# S10_Reset_Logic.net
KiCad netlist of a schematic drawn in Altium Designer
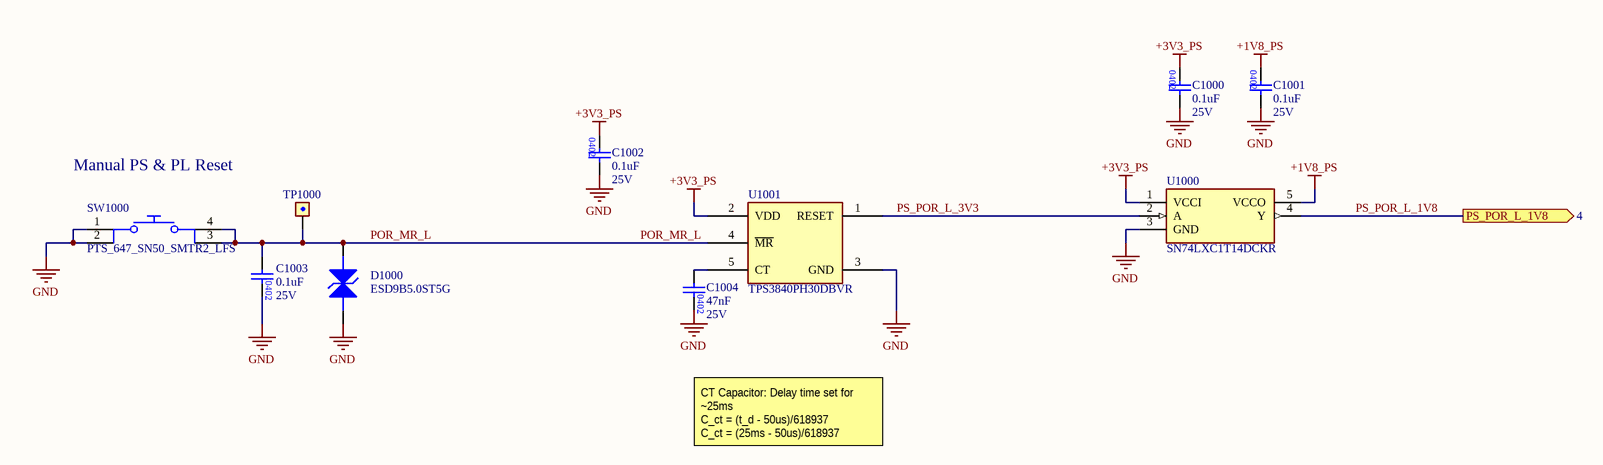
[diagram p0: S10_Reset_Logic.SchDoc]

(export (version "E")
  (design (tool "Eeschema 10.0.6"))
  (components
    (comp (ref "C1000")
      (value "0.1uF")
      (footprint "CAP0402")
      (description "CAP CER 0.1UF 25V X5R 0402")
      (fields
        (field (name "MANUFACTURER") "Samsung Electro-Mechanics")
        (field (name "TOLERANCE") "10%")
        (field (name "VOLTAGE RATING") "25V")
      )
      (libsource (lib "OpenCore_Sch_Lib") (part "CAP_CL05A104KA5NNNC"))
    )
    (comp (ref "C1001")
      (value "0.1uF")
      (footprint "CAP0402")
      (description "CAP CER 0.1UF 25V X5R 0402")
      (fields
        (field (name "MANUFACTURER") "Samsung Electro-Mechanics")
        (field (name "TOLERANCE") "10%")
        (field (name "VOLTAGE RATING") "25V")
      )
      (libsource (lib "OpenCore_Sch_Lib") (part "CAP_CL05A104KA5NNNC"))
    )
    (comp (ref "C1002")
      (value "0.1uF")
      (footprint "CAP0402")
      (description "CAP CER 0.1UF 25V X5R 0402")
      (fields
        (field (name "MANUFACTURER") "Samsung Electro-Mechanics")
        (field (name "TOLERANCE") "10%")
        (field (name "VOLTAGE RATING") "25V")
      )
      (libsource (lib "OpenCore_Sch_Lib") (part "CAP_CL05A104KA5NNNC"))
    )
    (comp (ref "C1003")
      (value "0.1uF")
      (footprint "CAP0402")
      (description "CAP CER 0.1UF 25V X5R 0402")
      (fields
        (field (name "MANUFACTURER") "Samsung Electro-Mechanics")
        (field (name "TOLERANCE") "10%")
        (field (name "VOLTAGE RATING") "25V")
      )
      (libsource (lib "OpenCore_Sch_Lib") (part "CAP_CL05A104KA5NNNC"))
    )
    (comp (ref "C1004")
      (value "47nF")
      (footprint "CAP0402")
      (description "CAP CER 0.047UF 25V X7R 0402")
      (fields
        (field (name "MANUFACTURER") "Murata Electronics")
        (field (name "TOLERANCE") "10%")
        (field (name "VOLTAGE RATING") "25V")
      )
      (libsource (lib "OpenCore_Sch_Lib") (part "CAP_GRM155R71E473KA88D"))
    )
    (comp (ref "D1000")
      (value "ESD9B5.0ST5G")
      (footprint "ONSEMI_SOD-923")
      (description "TVS DIODE 5VWM SOD923")
      (fields (field (name "MANUFACTURER PART NUMBER") "ESD9B5.0ST5G"))
      (libsource (lib "OpenCore_Sch_Lib") (part "ESD9B5.0ST5G"))
    )
    (comp (ref "SW1000")
      (value "PTS_647_SN50_SMTR2_LFS")
      (footprint "TACTILE_SW_4.5MM")
      (description "SWITCH TACTILE SPST-NO 0.05A 12V")
      (libsource (lib "OpenCore_Sch_Lib") (part "PTS_647_SN50_SMTR2_LFS"))
    )
    (comp (ref "TP1000")
      (value "1mm Round Pad Testpoint")
      (footprint "TP_1MM")
      (libsource (lib "OpenCore_Sch_Lib") (part "TP_1MM"))
    )
    (comp (ref "U1000")
      (value "SN74LXC1T14DCKR")
      (footprint "TI_SC70_DCK0005A")
      (description "IC TRANSLATOR UNIDIR SC70-5")
      (libsource (lib "OpenCore_Sch_Lib") (part "SN74LXC1T14DCKR"))
    )
    (comp (ref "U1001")
      (value "TPS3840PH30DBVR")
      (footprint "TI_SOT23_DBV0005A")
      (description "IC SUPERVISOR 1 CHANNEL SOT23-5")
      (libsource (lib "OpenCore_Sch_Lib") (part "TPS3840PH30DBVR"))
    )
  )
  (nets
    (net (code "1") (name "+1V8_PS") (class "Default")
      (node (ref "C1001") (pin "1") (pinfunction "1_1") (pintype "passive"))
      (node (ref "U1000") (pin "5") (pinfunction "VCCO_5") (pintype "power_in"))
    )
    (net (code "2") (name "+3V3_PS") (class "Default")
      (node (ref "C1000") (pin "1") (pinfunction "1_1") (pintype "passive"))
      (node (ref "C1002") (pin "1") (pinfunction "1_1") (pintype "passive"))
      (node (ref "U1000") (pin "1") (pinfunction "VCCI_1") (pintype "power_in"))
      (node (ref "U1001") (pin "2") (pinfunction "VDD_2") (pintype "passive"))
    )
    (net (code "3") (name "/POR_MR_L") (class "Default")
      (node (ref "C1003") (pin "1") (pinfunction "1_1") (pintype "passive"))
      (node (ref "D1000") (pin "A") (pinfunction "Anode_A") (pintype "passive"))
      (node (ref "SW1000") (pin "3") (pinfunction "3_3") (pintype "passive"))
      (node (ref "SW1000") (pin "4") (pinfunction "4_4") (pintype "passive"))
      (node (ref "TP1000") (pin "1") (pinfunction "1_1") (pintype "passive"))
      (node (ref "U1001") (pin "4") (pinfunction "~{MR}_4") (pintype "passive"))
    )
    (net (code "4") (name "/PS_POR_L_1V8") (class "Default")
      (node (ref "U1000") (pin "4") (pinfunction "Y_4") (pintype "output"))
    )
    (net (code "5") (name "/PS_POR_L_3V3") (class "Default")
      (node (ref "U1000") (pin "2") (pinfunction "A_2") (pintype "input"))
      (node (ref "U1001") (pin "1") (pinfunction "RESET_1") (pintype "passive"))
    )
    (net (code "6") (name "GND") (class "Default")
      (node (ref "C1000") (pin "2") (pinfunction "2_2") (pintype "passive"))
      (node (ref "C1001") (pin "2") (pinfunction "2_2") (pintype "passive"))
      (node (ref "C1002") (pin "2") (pinfunction "2_2") (pintype "passive"))
      (node (ref "C1003") (pin "2") (pinfunction "2_2") (pintype "passive"))
      (node (ref "C1004") (pin "2") (pinfunction "2_2") (pintype "passive"))
      (node (ref "D1000") (pin "K") (pinfunction "Cathode_K") (pintype "passive"))
      (node (ref "SW1000") (pin "1") (pinfunction "1_1") (pintype "passive"))
      (node (ref "SW1000") (pin "2") (pinfunction "2_2") (pintype "passive"))
      (node (ref "U1000") (pin "3") (pinfunction "GND_3") (pintype "power_in"))
      (node (ref "U1001") (pin "3") (pinfunction "GND_3") (pintype "passive"))
    )
    (net (code "7") (name "Net-(U1001-CT)") (class "Default")
      (node (ref "C1004") (pin "1") (pinfunction "1_1") (pintype "passive"))
      (node (ref "U1001") (pin "5") (pinfunction "CT_5") (pintype "passive"))
    )
  )
)
